# dsau-dds-clock.net
KiCad netlist of a schematic drawn in Altium Designer
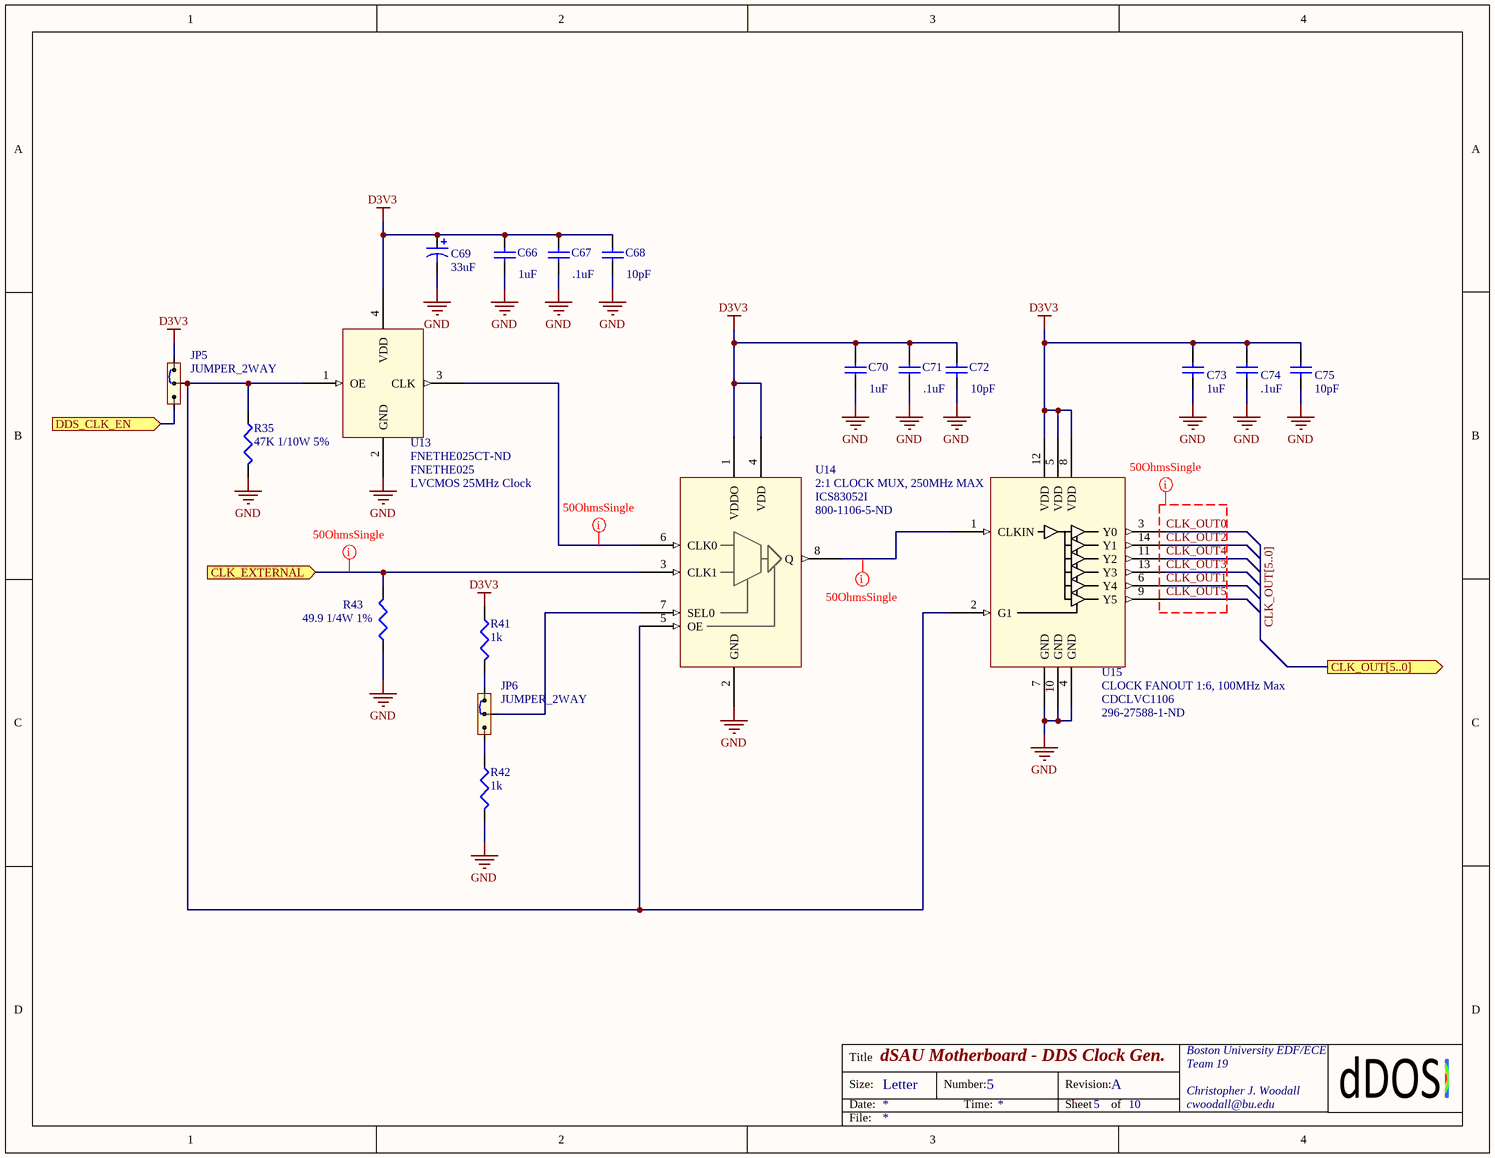
[diagram p0: dsau-dds-clock.SchDoc]

(export (version "E")
  (design (tool "Eeschema 10.0.6"))
  (components
    (comp (ref "C66")
      (value "1uF")
      (footprint "CAPC2012L")
      (description "Capacitor")
      (fields
        (field (name "MANUFACTURER") "Yageo")
        (field (name "MANUFACTURER PART NUMBER") "CC0805KKX7R7BB105")
        (field (name "PUBLISHER") "Altium Limited")
      )
      (libsource (lib "Miscellaneous Devices") (part "Cap"))
    )
    (comp (ref "C67")
      (value ".1uF")
      (footprint "CAPC1608L")
      (description "Capacitor")
      (fields
        (field (name "MANUFACTURER") "Yageo")
        (field (name "MANUFACTURER PART NUMBER") "CC0603ZRY5V9BB104")
        (field (name "PUBLISHER") "Altium Limited")
      )
      (libsource (lib "Miscellaneous Devices") (part "Cap"))
    )
    (comp (ref "C68")
      (value "10pF")
      (footprint "CAPC1608L")
      (description "Capacitor")
      (fields
        (field (name "MANUFACTURER") "Samsung Electro-Mechanics America, Inc")
        (field (name "MANUFACTURER PART NUMBER") "CL10C100JB8NCNC")
        (field (name "PUBLISHER") "Altium Limited")
      )
      (libsource (lib "Miscellaneous Devices") (part "Cap"))
    )
    (comp (ref "C69")
      (value "33uF")
      (footprint "CAPC2012L")
      (description "Polarized Capacitor (Surface Mount)")
      (fields
        (field (name "MANUFACTURER") "AVX Corporation")
        (field (name "MANUFACTURER PART NUMBER") "TPSA336K006R0600")
        (field (name "PUBLISHER") "Altium Limited")
      )
      (libsource (lib "Miscellaneous Devices") (part "Cap Pol3"))
    )
    (comp (ref "C70")
      (value "1uF")
      (footprint "CAPC2012L")
      (description "Capacitor")
      (fields
        (field (name "MANUFACTURER") "Yageo")
        (field (name "MANUFACTURER PART NUMBER") "CC0805KKX7R7BB105")
        (field (name "PUBLISHER") "Altium Limited")
      )
      (libsource (lib "Miscellaneous Devices") (part "Cap"))
    )
    (comp (ref "C71")
      (value ".1uF")
      (footprint "CAPC1608L")
      (description "Capacitor")
      (fields
        (field (name "MANUFACTURER") "Yageo")
        (field (name "MANUFACTURER PART NUMBER") "CC0603ZRY5V9BB104")
        (field (name "PUBLISHER") "Altium Limited")
      )
      (libsource (lib "Miscellaneous Devices") (part "Cap"))
    )
    (comp (ref "C72")
      (value "10pF")
      (footprint "CAPC1608L")
      (description "Capacitor")
      (fields
        (field (name "MANUFACTURER") "Samsung Electro-Mechanics America, Inc")
        (field (name "MANUFACTURER PART NUMBER") "CL10C100JB8NCNC")
        (field (name "PUBLISHER") "Altium Limited")
      )
      (libsource (lib "Miscellaneous Devices") (part "Cap"))
    )
    (comp (ref "C73")
      (value "1uF")
      (footprint "CAPC2012L")
      (description "Capacitor")
      (fields
        (field (name "MANUFACTURER") "Yageo")
        (field (name "MANUFACTURER PART NUMBER") "CC0805KKX7R7BB105")
        (field (name "PUBLISHER") "Altium Limited")
      )
      (libsource (lib "Miscellaneous Devices") (part "Cap"))
    )
    (comp (ref "C74")
      (value ".1uF")
      (footprint "CAPC1608L")
      (description "Capacitor")
      (fields
        (field (name "MANUFACTURER") "Yageo")
        (field (name "MANUFACTURER PART NUMBER") "CC0603ZRY5V9BB104")
        (field (name "PUBLISHER") "Altium Limited")
      )
      (libsource (lib "Miscellaneous Devices") (part "Cap"))
    )
    (comp (ref "C75")
      (value "10pF")
      (footprint "CAPC1608L")
      (description "Capacitor")
      (fields
        (field (name "MANUFACTURER") "Samsung Electro-Mechanics America, Inc")
        (field (name "MANUFACTURER PART NUMBER") "CL10C100JB8NCNC")
        (field (name "PUBLISHER") "Altium Limited")
      )
      (libsource (lib "Miscellaneous Devices") (part "Cap"))
    )
    (comp (ref "JP5")
      (value "JUMPER_2WAY")
      (footprint "HDR1X3")
      (libsource (lib "dsau-motherboard") (part "JUMPER_2WAY"))
    )
    (comp (ref "JP6")
      (value "JUMPER_2WAY")
      (footprint "HDR1X3")
      (libsource (lib "dsau-motherboard") (part "JUMPER_2WAY"))
    )
    (comp (ref "R35")
      (value "47K 1/10W 5%")
      (footprint "RESC1608L")
      (description "Resistor")
      (fields
        (field (name "MANUFACTURER") "Yageo")
        (field (name "MANUFACTURER PART NUMBER") "311-47kGRCT-ND")
        (field (name "PUBLISHER") "Altium Limited")
      )
      (libsource (lib "Miscellaneous Devices") (part "Res3"))
    )
    (comp (ref "R41")
      (value "1k")
      (footprint "RESC1608L")
      (description "Resistor")
      (fields
        (field (name "MANUFACTURER") "Yageo")
        (field (name "MANUFACTURER PART NUMBER") "RC0603JR-071KL")
        (field (name "PUBLISHER") "Altium Limited")
      )
      (libsource (lib "Miscellaneous Devices") (part "Res3"))
    )
    (comp (ref "R42")
      (value "1k")
      (footprint "RESC1608L")
      (description "Resistor")
      (fields
        (field (name "MANUFACTURER") "Yageo")
        (field (name "MANUFACTURER PART NUMBER") "RC0603JR-071KL")
        (field (name "PUBLISHER") "Altium Limited")
      )
      (libsource (lib "Miscellaneous Devices") (part "Res3"))
    )
    (comp (ref "R43")
      (value "49.9 1/4W 1%")
      (footprint "RESC3216L")
      (description "Resistor")
      (fields
        (field (name "MANUFACTURER") "Panasonic Electronic Components")
        (field (name "MANUFACTURER PART NUMBER") "ERJ-8ENF49R9V")
        (field (name "PUBLISHER") "Altium Limited")
      )
      (libsource (lib "Miscellaneous Devices") (part "Res3"))
    )
    (comp (ref "U13")
      (value "LVCMOS 25MHz Clock")
      (footprint "FNETHE025_4SMD")
      (fields
        (field (name "MANUFACTURER") "Pericom")
        (field (name "MANUFACTURER PART NUMBER") "FNETHE025")
        (field (name "SUPPLIER PART NUMBER 1") "FNETHE025CT-ND")
      )
      (libsource (lib "dsau-motherboard") (part "FNETHE025"))
    )
    (comp (ref "U14")
      (value "2:1 CLOCK MUX, 250MHz MAX")
      (footprint "SOP65P780-8M")
      (fields
        (field (name "MANUFACTURER") "IDT")
        (field (name "MANUFACTURER PART NUMBER") "ICS83052I")
        (field (name "SUPPLIER PART NUMBER 1") "800-1106-5-ND")
      )
      (libsource (lib "dsau-motherboard") (part "ICS83052I"))
    )
    (comp (ref "U15")
      (value "CLOCK FANOUT 1:6, 100MHz Max")
      (footprint "TSOP65P640-14AM")
      (description "Clock Fanout 1:6, 100MHz low-skew")
      (fields
        (field (name "MANUFACTURER") "Texas Instruments")
        (field (name "MANUFACTURER PART NUMBER") "CDCLVC1106")
        (field (name "SUPPLIER PART NUMBER 1") "296-27588-1-ND")
      )
      (libsource (lib "dsau-motherboard") (part "CDCLVC1106"))
    )
  )
  (nets
    (net (code "1") (name "/CLK_EXTERNAL") (class "Default")
      (node (ref "R43") (pin "2") (pinfunction "2_2") (pintype "passive"))
      (node (ref "U14") (pin "3") (pinfunction "CLK1_3") (pintype "input"))
    )
    (net (code "2") (name "/CLK_OUT0") (class "Default")
      (node (ref "U15") (pin "3") (pinfunction "Y0_3") (pintype "output"))
    )
    (net (code "3") (name "/CLK_OUT1") (class "Default")
      (node (ref "U15") (pin "6") (pinfunction "Y4_6") (pintype "output"))
    )
    (net (code "4") (name "/CLK_OUT2") (class "Default")
      (node (ref "U15") (pin "14") (pinfunction "Y1_14") (pintype "output"))
    )
    (net (code "5") (name "/CLK_OUT3") (class "Default")
      (node (ref "U15") (pin "13") (pinfunction "Y3_13") (pintype "output"))
    )
    (net (code "6") (name "/CLK_OUT4") (class "Default")
      (node (ref "U15") (pin "11") (pinfunction "Y2_11") (pintype "output"))
    )
    (net (code "7") (name "/CLK_OUT5") (class "Default")
      (node (ref "U15") (pin "9") (pinfunction "Y5_9") (pintype "output"))
    )
    (net (code "9") (name "/DDS_CLK_EN") (class "Default") (node (ref "JP5") (pin "3") (pintype "passive")))
    (net (code "10") (name "D3V3") (class "Default")
      (node (ref "C66") (pin "1") (pinfunction "1_1") (pintype "passive"))
      (node (ref "C67") (pin "1") (pinfunction "1_1") (pintype "passive"))
      (node (ref "C68") (pin "1") (pinfunction "1_1") (pintype "passive"))
      (node (ref "C69") (pin "1") (pinfunction "1_1") (pintype "passive"))
      (node (ref "C70") (pin "1") (pinfunction "1_1") (pintype "passive"))
      (node (ref "C71") (pin "1") (pinfunction "1_1") (pintype "passive"))
      (node (ref "C72") (pin "1") (pinfunction "1_1") (pintype "passive"))
      (node (ref "C73") (pin "1") (pinfunction "1_1") (pintype "passive"))
      (node (ref "C74") (pin "1") (pinfunction "1_1") (pintype "passive"))
      (node (ref "C75") (pin "1") (pinfunction "1_1") (pintype "passive"))
      (node (ref "JP5") (pin "1") (pintype "passive"))
      (node (ref "R41") (pin "1") (pinfunction "1_1") (pintype "passive"))
      (node (ref "U13") (pin "4") (pinfunction "VDD_4") (pintype "power_in"))
      (node (ref "U14") (pin "1") (pinfunction "VDDO_1") (pintype "power_in"))
      (node (ref "U14") (pin "4") (pinfunction "VDD_4") (pintype "power_in"))
      (node (ref "U15") (pin "12") (pinfunction "VDD_12") (pintype "power_in"))
      (node (ref "U15") (pin "5") (pinfunction "VDD_5") (pintype "power_in"))
      (node (ref "U15") (pin "8") (pinfunction "VDD_8") (pintype "power_in"))
    )
    (net (code "11") (name "GND") (class "Default")
      (node (ref "C66") (pin "2") (pinfunction "2_2") (pintype "passive"))
      (node (ref "C67") (pin "2") (pinfunction "2_2") (pintype "passive"))
      (node (ref "C68") (pin "2") (pinfunction "2_2") (pintype "passive"))
      (node (ref "C69") (pin "2") (pinfunction "2_2") (pintype "passive"))
      (node (ref "C70") (pin "2") (pinfunction "2_2") (pintype "passive"))
      (node (ref "C71") (pin "2") (pinfunction "2_2") (pintype "passive"))
      (node (ref "C72") (pin "2") (pinfunction "2_2") (pintype "passive"))
      (node (ref "C73") (pin "2") (pinfunction "2_2") (pintype "passive"))
      (node (ref "C74") (pin "2") (pinfunction "2_2") (pintype "passive"))
      (node (ref "C75") (pin "2") (pinfunction "2_2") (pintype "passive"))
      (node (ref "R35") (pin "2") (pinfunction "2_2") (pintype "passive"))
      (node (ref "R42") (pin "2") (pinfunction "2_2") (pintype "passive"))
      (node (ref "R43") (pin "1") (pinfunction "1_1") (pintype "passive"))
      (node (ref "U13") (pin "2") (pinfunction "GND_2") (pintype "power_in"))
      (node (ref "U14") (pin "2") (pinfunction "GND_2") (pintype "power_in"))
      (node (ref "U15") (pin "10") (pinfunction "GND_10") (pintype "power_in"))
      (node (ref "U15") (pin "4") (pinfunction "GND_4") (pintype "power_in"))
      (node (ref "U15") (pin "7") (pinfunction "GND_7") (pintype "power_in"))
    )
    (net (code "12") (name "Net-(JP6-Pad1)") (class "Default")
      (node (ref "JP6") (pin "1") (pintype "passive"))
      (node (ref "R41") (pin "2") (pinfunction "2_2") (pintype "passive"))
    )
    (net (code "13") (name "Net-(JP6-Pad3)") (class "Default")
      (node (ref "JP6") (pin "3") (pintype "passive"))
      (node (ref "R42") (pin "1") (pinfunction "1_1") (pintype "passive"))
    )
    (net (code "14") (name "Net-(U13-CLK)") (class "Default")
      (node (ref "U13") (pin "3") (pinfunction "CLK_3") (pintype "output"))
      (node (ref "U14") (pin "6") (pinfunction "CLK0_6") (pintype "input"))
    )
    (net (code "15") (name "Net-(U13-OE)") (class "Default")
      (node (ref "JP5") (pin "2") (pintype "passive"))
      (node (ref "R35") (pin "1") (pinfunction "1_1") (pintype "passive"))
      (node (ref "U13") (pin "1") (pinfunction "OE_1") (pintype "input"))
      (node (ref "U14") (pin "5") (pinfunction "OE_5") (pintype "input"))
      (node (ref "U15") (pin "2") (pinfunction "G1_2") (pintype "input"))
    )
    (net (code "16") (name "Net-(U14-Q)") (class "Default")
      (node (ref "U14") (pin "8") (pinfunction "Q_8") (pintype "output"))
      (node (ref "U15") (pin "1") (pinfunction "CLKIN_1") (pintype "input"))
    )
    (net (code "17") (name "Net-(U14-SEL0)") (class "Default")
      (node (ref "JP6") (pin "2") (pintype "passive"))
      (node (ref "U14") (pin "7") (pinfunction "SEL0_7") (pintype "input"))
    )
  )
)
